# POWER.net
KiCad netlist of a schematic drawn in Altium Designer
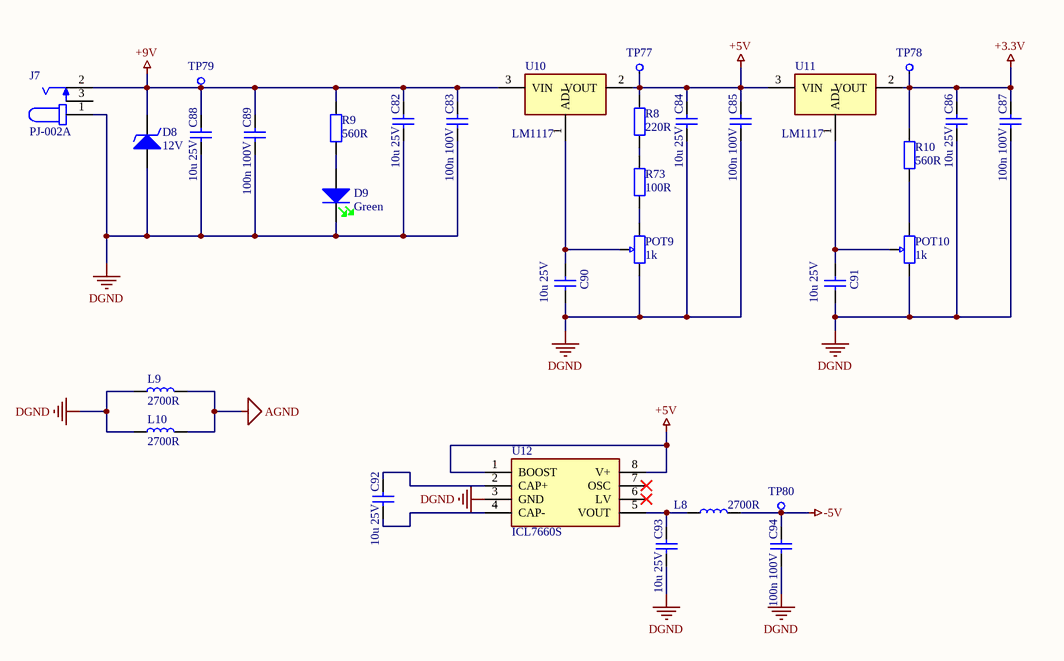
[diagram p0: POWER.SchDoc]

(export (version "E")
  (design (tool "Eeschema 10.0.6"))
  (components
    (comp (ref "C82")
      (value "10u 25V")
      (footprint "FOOTPRINTS:CAPACITOR 0805")
      (description "Capacitor: ceramic; MLCC; 10uF; 25V; X5R; ±10%; SMD; 0805")
      (fields
        (field (name "MANUFACTURER") "MURATA")
        (field (name "MANUFACTURER PART NUMBER") "GRM21BR61E106KA73K")
      )
      (libsource (lib "SYMBOLS") (part "Capacitor 10u 25V 10% X5R 0805"))
    )
    (comp (ref "C83")
      (value "100n 100V")
      (footprint "FOOTPRINTS:CAPACITOR 0805")
      (description "Capacitor: ceramic; MLCC; 100nF; 100V; X7R; ±10%; SMD; 0805")
      (fields
        (field (name "MANUFACTURER") "YAGEO")
        (field (name "MANUFACTURER PART NUMBER") "CC0805KKX7R0BB104")
      )
      (libsource (lib "SYMBOLS") (part "Capacitor 100n 100V 10% X7R 0805"))
    )
    (comp (ref "C84")
      (value "10u 25V")
      (footprint "FOOTPRINTS:CAPACITOR 0805")
      (description "Capacitor: ceramic; MLCC; 10uF; 25V; X5R; ±10%; SMD; 0805")
      (fields
        (field (name "MANUFACTURER") "MURATA")
        (field (name "MANUFACTURER PART NUMBER") "GRM21BR61E106KA73K")
      )
      (libsource (lib "SYMBOLS") (part "Capacitor 10u 25V 10% X5R 0805"))
    )
    (comp (ref "C85")
      (value "100n 100V")
      (footprint "FOOTPRINTS:CAPACITOR 0805")
      (description "Capacitor: ceramic; MLCC; 100nF; 100V; X7R; ±10%; SMD; 0805")
      (fields
        (field (name "MANUFACTURER") "YAGEO")
        (field (name "MANUFACTURER PART NUMBER") "CC0805KKX7R0BB104")
      )
      (libsource (lib "SYMBOLS") (part "Capacitor 100n 100V 10% X7R 0805"))
    )
    (comp (ref "C86")
      (value "10u 25V")
      (footprint "FOOTPRINTS:CAPACITOR 0805")
      (description "Capacitor: ceramic; MLCC; 10uF; 25V; X5R; ±10%; SMD; 0805")
      (fields
        (field (name "MANUFACTURER") "MURATA")
        (field (name "MANUFACTURER PART NUMBER") "GRM21BR61E106KA73K")
      )
      (libsource (lib "SYMBOLS") (part "Capacitor 10u 25V 10% X5R 0805"))
    )
    (comp (ref "C87")
      (value "100n 100V")
      (footprint "FOOTPRINTS:CAPACITOR 0805")
      (description "Capacitor: ceramic; MLCC; 100nF; 100V; X7R; ±10%; SMD; 0805")
      (fields
        (field (name "MANUFACTURER") "YAGEO")
        (field (name "MANUFACTURER PART NUMBER") "CC0805KKX7R0BB104")
      )
      (libsource (lib "SYMBOLS") (part "Capacitor 100n 100V 10% X7R 0805"))
    )
    (comp (ref "C88")
      (value "10u 25V")
      (footprint "FOOTPRINTS:CAPACITOR 0805")
      (description "Capacitor: ceramic; MLCC; 10uF; 25V; X5R; ±10%; SMD; 0805")
      (fields
        (field (name "MANUFACTURER") "MURATA")
        (field (name "MANUFACTURER PART NUMBER") "GRM21BR61E106KA73K")
      )
      (libsource (lib "SYMBOLS") (part "Capacitor 10u 25V 10% X5R 0805"))
    )
    (comp (ref "C89")
      (value "100n 100V")
      (footprint "FOOTPRINTS:CAPACITOR 0805")
      (description "Capacitor: ceramic; MLCC; 100nF; 100V; X7R; ±10%; SMD; 0805")
      (fields
        (field (name "MANUFACTURER") "YAGEO")
        (field (name "MANUFACTURER PART NUMBER") "CC0805KKX7R0BB104")
      )
      (libsource (lib "SYMBOLS") (part "Capacitor 100n 100V 10% X7R 0805"))
    )
    (comp (ref "C90")
      (value "10u 25V")
      (footprint "FOOTPRINTS:CAPACITOR 0805")
      (description "Capacitor: ceramic; MLCC; 10uF; 25V; X5R; ±10%; SMD; 0805")
      (fields
        (field (name "MANUFACTURER") "MURATA")
        (field (name "MANUFACTURER PART NUMBER") "GRM21BR61E106KA73K")
      )
      (libsource (lib "SYMBOLS") (part "Capacitor 10u 25V 10% X5R 0805"))
    )
    (comp (ref "C91")
      (value "10u 25V")
      (footprint "FOOTPRINTS:CAPACITOR 0805")
      (description "Capacitor: ceramic; MLCC; 10uF; 25V; X5R; ±10%; SMD; 0805")
      (fields
        (field (name "MANUFACTURER") "MURATA")
        (field (name "MANUFACTURER PART NUMBER") "GRM21BR61E106KA73K")
      )
      (libsource (lib "SYMBOLS") (part "Capacitor 10u 25V 10% X5R 0805"))
    )
    (comp (ref "C92")
      (value "10u 25V")
      (footprint "FOOTPRINTS:CAPACITOR 0805")
      (description "Capacitor: ceramic; MLCC; 10uF; 25V; X5R; ±10%; SMD; 0805")
      (fields
        (field (name "MANUFACTURER") "MURATA")
        (field (name "MANUFACTURER PART NUMBER") "GRM21BR61E106KA73K")
      )
      (libsource (lib "SYMBOLS") (part "Capacitor 10u 25V 10% X5R 0805"))
    )
    (comp (ref "C93")
      (value "10u 25V")
      (footprint "FOOTPRINTS:CAPACITOR 0805")
      (description "Capacitor: ceramic; MLCC; 10uF; 25V; X5R; ±10%; SMD; 0805")
      (fields
        (field (name "MANUFACTURER") "MURATA")
        (field (name "MANUFACTURER PART NUMBER") "GRM21BR61E106KA73K")
      )
      (libsource (lib "SYMBOLS") (part "Capacitor 10u 25V 10% X5R 0805"))
    )
    (comp (ref "C94")
      (value "100n 100V")
      (footprint "FOOTPRINTS:CAPACITOR 0805")
      (description "Capacitor: ceramic; MLCC; 100nF; 100V; X7R; ±10%; SMD; 0805")
      (fields
        (field (name "MANUFACTURER") "YAGEO")
        (field (name "MANUFACTURER PART NUMBER") "CC0805KKX7R0BB104")
      )
      (libsource (lib "SYMBOLS") (part "Capacitor 100n 100V 10% X7R 0805"))
    )
    (comp (ref "D8")
      (value "12V")
      (footprint "FOOTPRINTS:SOD-80 DO-231AA")
      (description "Zener Diodes 12 Volt 0.5W 5%")
      (fields
        (field (name "MANUFACTURER") "Vishay Semiconductors")
        (field (name "MANUFACTURER PART NUMBER") "BZT55C12")
      )
      (libsource (lib "SYMBOLS") (part "Diode 12V 0.5W SOD80 Zener BZT55C1"))
    )
    (comp (ref "D9")
      (value "Green")
      (footprint "FOOTPRINTS:LED 0805")
      (description "Standard LEDs - SMD WL-SMCW SMDMono TpVw Waterclr 0805 Green")
      (fields
        (field (name "MANUFACTURER") "Wurth Elektronik")
        (field (name "MANUFACTURER PART NUMBER") "150080GS75000")
      )
      (libsource (lib "SYMBOLS") (part "Diode LED Green 0805 SMD 20mA"))
    )
    (comp (ref "J7")
      (value "PJ-002A")
      (footprint "FOOTPRINTS:Mechanical CUI_PJ-002A")
      (description "DC Power Connectors Power Jacks")
      (fields (field (name "MANUFACTURER") "https://pl.mouser.com/datasheet/2/670/pj_002a-1778764.pdf"))
      (libsource (lib "SYMBOLS") (part "Mechanical DC Power Connectors Power Jacks"))
    )
    (comp (ref "L8")
      (value "2700R")
      (footprint "FOOTPRINTS:FERRITE 0805")
      (description "Ferrite: bead; 2700Ω; SMD; 200mA; 0805; -55÷125°C")
      (fields
        (field (name "MANUFACTURER") "MURATA")
        (field (name "MANUFACTURER PART NUMBER") "BLM21BD272SN1L")
      )
      (libsource (lib "SYMBOLS") (part "Inductor Ferrite Bead 2700Ω 0805 0.2A"))
    )
    (comp (ref "L9")
      (value "2700R")
      (footprint "FOOTPRINTS:FERRITE 0805")
      (description "Ferrite: bead; 2700Ω; SMD; 200mA; 0805; -55÷125°C")
      (fields
        (field (name "MANUFACTURER") "MURATA")
        (field (name "MANUFACTURER PART NUMBER") "BLM21BD272SN1L")
      )
      (libsource (lib "SYMBOLS") (part "Inductor Ferrite Bead 2700Ω 0805 0.2A"))
    )
    (comp (ref "L10")
      (value "2700R")
      (footprint "FOOTPRINTS:FERRITE 0805")
      (description "Ferrite: bead; 2700Ω; SMD; 200mA; 0805; -55÷125°C")
      (fields
        (field (name "MANUFACTURER") "MURATA")
        (field (name "MANUFACTURER PART NUMBER") "BLM21BD272SN1L")
      )
      (libsource (lib "SYMBOLS") (part "Inductor Ferrite Bead 2700Ω 0805 0.2A"))
    )
    (comp (ref "POT9")
      (value "1k")
      (footprint "FOOTPRINTS:POTENTIOMETER TC33X")
      (description "Trimmer Resistors - SMD TRIMMER-3MM OPEN FRAME")
      (fields (field (name "MANUFACTURER") "Bourns") (field (name "MANUFACTURER PART NUMBER") "TC33X-1-102E"))
      (libsource (lib "SYMBOLS") (part "Potentiometer PCB 1k SMD TC33X-1-102E"))
    )
    (comp (ref "POT10")
      (value "1k")
      (footprint "FOOTPRINTS:POTENTIOMETER TC33X")
      (description "Trimmer Resistors - SMD TRIMMER-3MM OPEN FRAME")
      (fields (field (name "MANUFACTURER") "Bourns") (field (name "MANUFACTURER PART NUMBER") "TC33X-1-102E"))
      (libsource (lib "SYMBOLS") (part "Potentiometer PCB 1k SMD TC33X-1-102E"))
    )
    (comp (ref "R8")
      (value "220R")
      (footprint "FOOTPRINTS:RESISTOR 0805")
      (description "Resistor: thick film; SMD; 0805; 220Ω; 0.125W; ±1%; -55÷155°C")
      (fields
        (field (name "MANUFACTURER") "Yageo")
        (field (name "MANUFACTURER PART NUMBER") "RC0805FR-07220R")
      )
      (libsource (lib "SYMBOLS") (part "Resistor 220R 1% 1/8W 0805"))
    )
    (comp (ref "R9")
      (value "560R")
      (footprint "FOOTPRINTS:RESISTOR 0805")
      (description "Resistor: thick film; SMD; 0805; 560Ω; 0.125W; ±1%; -55÷155°C")
      (fields
        (field (name "MANUFACTURER") "Yageo")
        (field (name "MANUFACTURER PART NUMBER") "RC0805FR-07560R")
      )
      (libsource (lib "SYMBOLS") (part "Resistor 560R 1% 1/8W 0805"))
    )
    (comp (ref "R10")
      (value "560R")
      (footprint "FOOTPRINTS:RESISTOR 0805")
      (description "Resistor: thick film; SMD; 0805; 560Ω; 0.125W; ±1%; -55÷155°C")
      (fields
        (field (name "MANUFACTURER") "Yageo")
        (field (name "MANUFACTURER PART NUMBER") "RC0805FR-07560R")
      )
      (libsource (lib "SYMBOLS") (part "Resistor 560R 1% 1/8W 0805"))
    )
    (comp (ref "R73")
      (value "100R")
      (footprint "FOOTPRINTS:RESISTOR 0805")
      (description "Resistor: thick film; SMD; 0805; 100Ω; 0.125W; ±1%; -55÷155°C")
      (fields
        (field (name "MANUFACTURER") "Yageo")
        (field (name "MANUFACTURER PART NUMBER") "RC0805FR-07100R")
      )
      (libsource (lib "SYMBOLS") (part "Resistor 100R 1% 1/8W 0805"))
    )
    (comp (ref "TP77")
      (value "1mm")
      (footprint "FOOTPRINTS:TEST POINT 1MM")
      (description "Tesp Point 1mm")
      (libsource (lib "SYMBOLS") (part "Mechanical Test Point 1mm"))
    )
    (comp (ref "TP78")
      (value "1mm")
      (footprint "FOOTPRINTS:TEST POINT 1MM")
      (description "Tesp Point 1mm")
      (libsource (lib "SYMBOLS") (part "Mechanical Test Point 1mm"))
    )
    (comp (ref "TP79")
      (value "1mm")
      (footprint "FOOTPRINTS:TEST POINT 1MM")
      (description "Tesp Point 1mm")
      (libsource (lib "SYMBOLS") (part "Mechanical Test Point 1mm"))
    )
    (comp (ref "TP80")
      (value "1mm")
      (footprint "FOOTPRINTS:TEST POINT 1MM")
      (description "Tesp Point 1mm")
      (libsource (lib "SYMBOLS") (part "Mechanical Test Point 1mm"))
    )
    (comp (ref "U10")
      (value "LM1117")
      (footprint "FOOTPRINTS:TO-252")
      (description "LDO Voltage Regulators 800MA LDO LINEAR REG")
      (fields
        (field (name "MANUFACTURER PART NUMBER") "LM1117DT-ADJ")
        (field (name "MANUFACTURER") "Texas Instruments")
      )
      (libsource (lib "SYMBOLS") (part "IC LDO ADJ 800mA TO-252 LM1117DT-ADJ"))
    )
    (comp (ref "U11")
      (value "LM1117")
      (footprint "FOOTPRINTS:TO-252")
      (description "LDO Voltage Regulators 800MA LDO LINEAR REG")
      (fields
        (field (name "MANUFACTURER PART NUMBER") "LM1117DT-ADJ")
        (field (name "MANUFACTURER") "Texas Instruments")
      )
      (libsource (lib "SYMBOLS") (part "IC LDO ADJ 800mA TO-252 LM1117DT-ADJ"))
    )
    (comp (ref "U12")
      (value "ICL7660S")
      (footprint "FOOTPRINTS:SOIC-8")
      (description "Switching Voltage Regulators ICL7660SCBA")
      (fields
        (field (name "MANUFACTURER") "Renesas / Intersil")
        (field (name "MANUFACTURER PART NUMBER") "ICL7660SCBAZ-T")
      )
      (libsource (lib "SYMBOLS") (part "IC Switching Voltage Regulators ICL7660S SOIC-8"))
    )
  )
  (nets
    (net (code "1") (name "+3.3V") (class "Default")
      (node (ref "C86") (pin "2") (pinfunction "2_2") (pintype "passive"))
      (node (ref "C87") (pin "2") (pinfunction "2_2") (pintype "passive"))
      (node (ref "R10") (pin "2") (pinfunction "2_2") (pintype "passive"))
      (node (ref "TP78") (pin "1") (pinfunction "1_1") (pintype "passive"))
      (node (ref "U11") (pin "2") (pinfunction "VOUT_2") (pintype "passive"))
    )
    (net (code "2") (name "+5V") (class "Default")
      (node (ref "C84") (pin "2") (pinfunction "2_2") (pintype "passive"))
      (node (ref "C85") (pin "2") (pinfunction "2_2") (pintype "passive"))
      (node (ref "R8") (pin "2") (pinfunction "2_2") (pintype "passive"))
      (node (ref "TP77") (pin "1") (pinfunction "1_1") (pintype "passive"))
      (node (ref "U10") (pin "2") (pinfunction "VOUT_2") (pintype "passive"))
      (node (ref "U11") (pin "3") (pinfunction "VIN_3") (pintype "passive"))
      (node (ref "U12") (pin "1") (pinfunction "BOOST_1") (pintype "passive"))
      (node (ref "U12") (pin "8") (pinfunction "V+_8") (pintype "passive"))
    )
    (net (code "3") (name "+9V") (class "Default")
      (node (ref "C82") (pin "2") (pinfunction "2_2") (pintype "passive"))
      (node (ref "C83") (pin "2") (pinfunction "2_2") (pintype "passive"))
      (node (ref "C88") (pin "2") (pinfunction "2_2") (pintype "passive"))
      (node (ref "C89") (pin "2") (pinfunction "2_2") (pintype "passive"))
      (node (ref "D8") (pin "2") (pinfunction "2_2") (pintype "passive"))
      (node (ref "J7") (pin "2") (pinfunction "2_2") (pintype "passive"))
      (node (ref "R9") (pin "2") (pinfunction "2_2") (pintype "passive"))
      (node (ref "TP79") (pin "1") (pinfunction "1_1") (pintype "passive"))
      (node (ref "U10") (pin "3") (pinfunction "VIN_3") (pintype "passive"))
    )
    (net (code "4") (name "-5V") (class "Default")
      (node (ref "C94") (pin "2") (pinfunction "2_2") (pintype "passive"))
      (node (ref "L8") (pin "2") (pinfunction "2_2") (pintype "passive"))
      (node (ref "TP80") (pin "1") (pinfunction "1_1") (pintype "passive"))
    )
    (net (code "5") (name "AGND") (class "Default")
      (node (ref "L10") (pin "2") (pinfunction "2_2") (pintype "passive"))
      (node (ref "L9") (pin "2") (pinfunction "2_2") (pintype "passive"))
    )
    (net (code "6") (name "DGND") (class "Default")
      (node (ref "C82") (pin "1") (pinfunction "1_1") (pintype "passive"))
      (node (ref "C83") (pin "1") (pinfunction "1_1") (pintype "passive"))
      (node (ref "C84") (pin "1") (pinfunction "1_1") (pintype "passive"))
      (node (ref "C85") (pin "1") (pinfunction "1_1") (pintype "passive"))
      (node (ref "C86") (pin "1") (pinfunction "1_1") (pintype "passive"))
      (node (ref "C87") (pin "1") (pinfunction "1_1") (pintype "passive"))
      (node (ref "C88") (pin "1") (pinfunction "1_1") (pintype "passive"))
      (node (ref "C89") (pin "1") (pinfunction "1_1") (pintype "passive"))
      (node (ref "C90") (pin "1") (pinfunction "1_1") (pintype "passive"))
      (node (ref "C91") (pin "1") (pinfunction "1_1") (pintype "passive"))
      (node (ref "C93") (pin "1") (pinfunction "1_1") (pintype "passive"))
      (node (ref "C94") (pin "1") (pinfunction "1_1") (pintype "passive"))
      (node (ref "D8") (pin "1") (pinfunction "1_1") (pintype "passive"))
      (node (ref "D9") (pin "2") (pinfunction "2_2") (pintype "passive"))
      (node (ref "J7") (pin "1") (pinfunction "1_1") (pintype "passive"))
      (node (ref "L10") (pin "1") (pinfunction "1_1") (pintype "passive"))
      (node (ref "L9") (pin "1") (pinfunction "1_1") (pintype "passive"))
      (node (ref "POT10") (pin "1") (pinfunction "1_1") (pintype "passive"))
      (node (ref "POT9") (pin "1") (pinfunction "1_1") (pintype "passive"))
      (node (ref "U12") (pin "3") (pinfunction "GND_3") (pintype "passive"))
    )
    (net (code "7") (name "Net-(D9-Pad1)") (class "Default")
      (node (ref "D9") (pin "1") (pinfunction "1_1") (pintype "passive"))
      (node (ref "R9") (pin "1") (pinfunction "1_1") (pintype "passive"))
    )
    (net (code "8") (name "Net-(POT9-Pad3)") (class "Default")
      (node (ref "POT9") (pin "3") (pinfunction "3_3") (pintype "passive"))
      (node (ref "R73") (pin "1") (pinfunction "1_1") (pintype "passive"))
    )
    (net (code "9") (name "Net-(POT10-Pad3)") (class "Default")
      (node (ref "POT10") (pin "3") (pinfunction "3_3") (pintype "passive"))
      (node (ref "R10") (pin "1") (pinfunction "1_1") (pintype "passive"))
    )
    (net (code "10") (name "Net-(R73-Pad2)") (class "Default")
      (node (ref "R73") (pin "2") (pinfunction "2_2") (pintype "passive"))
      (node (ref "R8") (pin "1") (pinfunction "1_1") (pintype "passive"))
    )
    (net (code "11") (name "Net-(U10-ADJ)") (class "Default")
      (node (ref "C90") (pin "2") (pinfunction "2_2") (pintype "passive"))
      (node (ref "POT9") (pin "2") (pinfunction "2_2") (pintype "passive"))
      (node (ref "U10") (pin "1") (pinfunction "ADJ_1") (pintype "passive"))
    )
    (net (code "12") (name "Net-(U11-ADJ)") (class "Default")
      (node (ref "C91") (pin "2") (pinfunction "2_2") (pintype "passive"))
      (node (ref "POT10") (pin "2") (pinfunction "2_2") (pintype "passive"))
      (node (ref "U11") (pin "1") (pinfunction "ADJ_1") (pintype "passive"))
    )
    (net (code "13") (name "Net-(U12-CAP+)") (class "Default")
      (node (ref "C92") (pin "2") (pinfunction "2_2") (pintype "passive"))
      (node (ref "U12") (pin "2") (pinfunction "CAP+_2") (pintype "passive"))
    )
    (net (code "14") (name "Net-(U12-CAP-)") (class "Default")
      (node (ref "C92") (pin "1") (pinfunction "1_1") (pintype "passive"))
      (node (ref "U12") (pin "4") (pinfunction "CAP-_4") (pintype "passive"))
    )
    (net (code "15") (name "Net-(U12-VOUT)") (class "Default")
      (node (ref "C93") (pin "2") (pinfunction "2_2") (pintype "passive"))
      (node (ref "L8") (pin "1") (pinfunction "1_1") (pintype "passive"))
      (node (ref "U12") (pin "5") (pinfunction "VOUT_5") (pintype "passive"))
    )
    (net (code "16") (name "unconnected-(J7-Pad3)") (class "Default")
      (node (ref "J7") (pin "3") (pinfunction "3_3") (pintype "passive"))
    )
    (net (code "17") (name "unconnected-(U12-LV-Pad6)") (class "Default")
      (node (ref "U12") (pin "6") (pinfunction "LV_6") (pintype "passive+no_connect"))
    )
    (net (code "18") (name "unconnected-(U12-OSC-Pad7)") (class "Default")
      (node (ref "U12") (pin "7") (pinfunction "OSC_7") (pintype "passive+no_connect"))
    )
  )
)
